# Shield-0_6.net
KiCad netlist of a schematic drawn in EAGLE
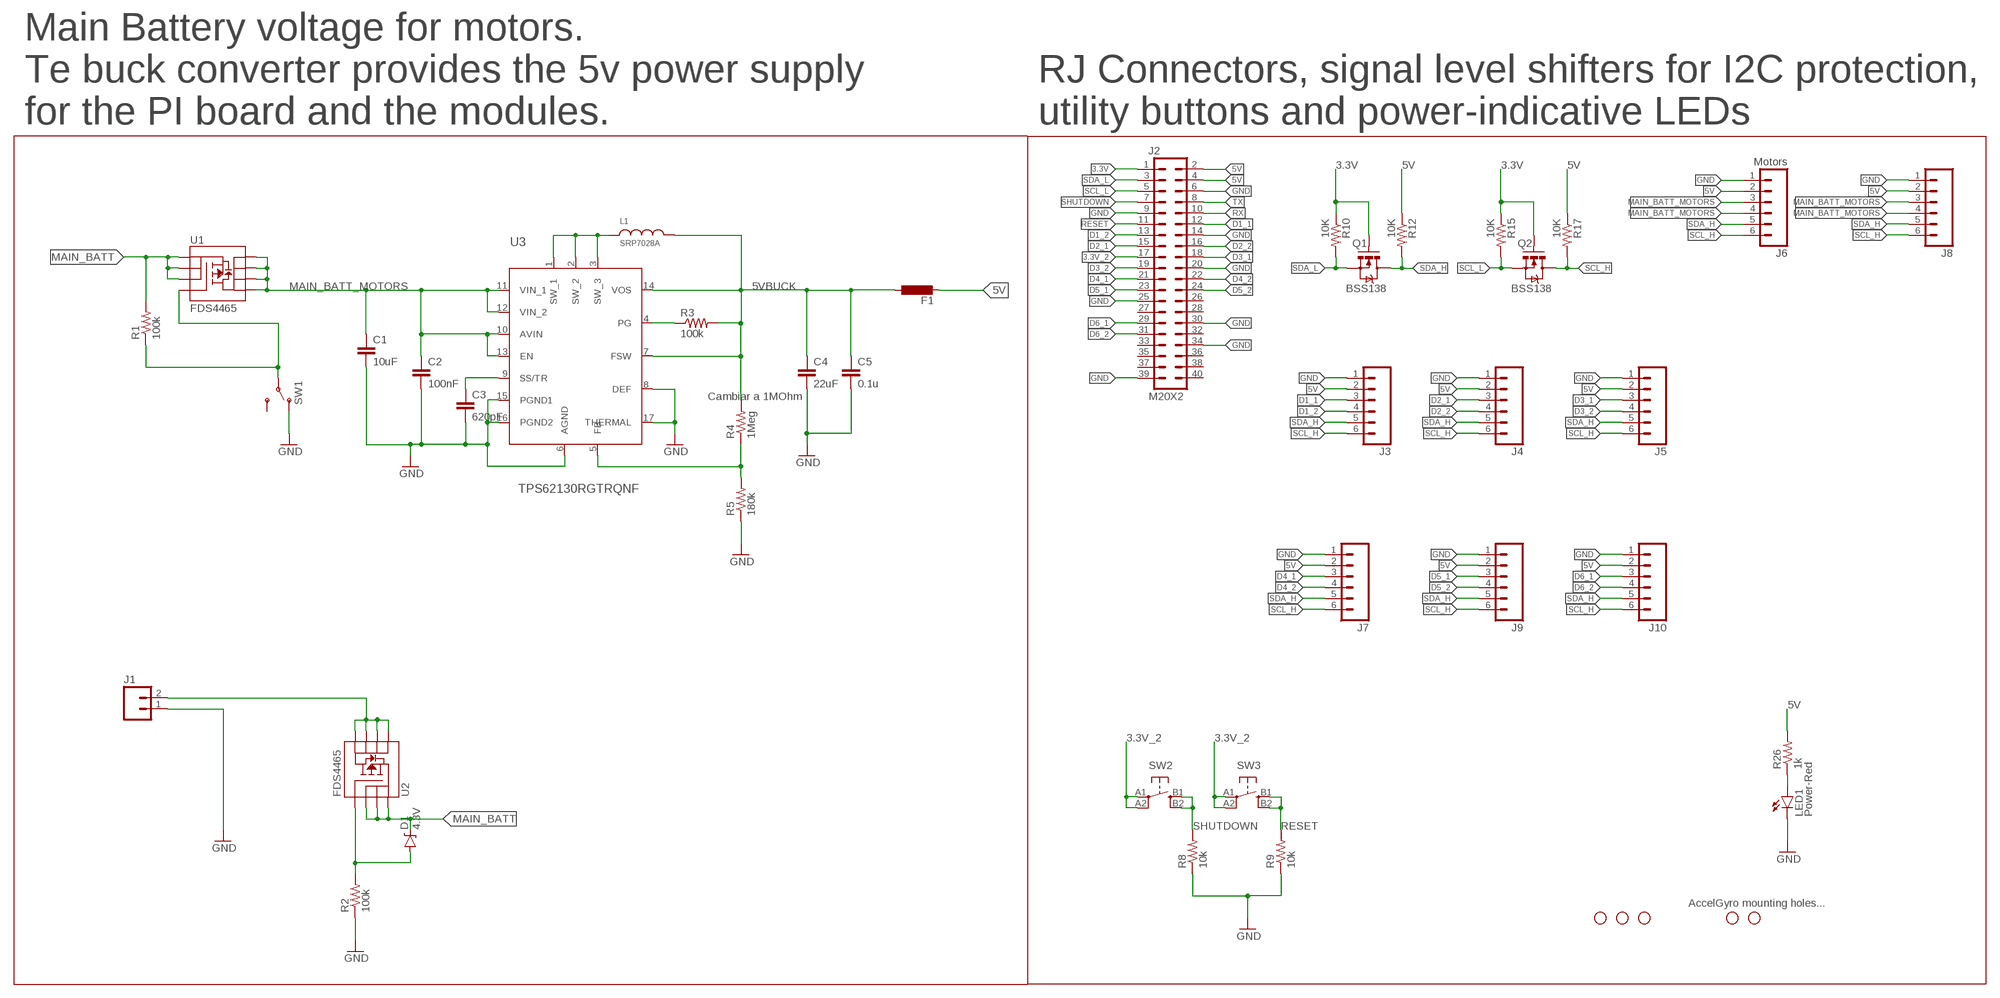
[diagram p0: schematic, sheet 1]

(export (version "E")
  (design (tool "Eeschema 10.0.6"))
  (components
    (comp (ref "C1")
      (value "10uF")
      (footprint "eagle-import:0603-CAP")
      (libsource (lib "eagle-import") (part "CAP0603-CAP"))
    )
    (comp (ref "C2")
      (value "100nF")
      (footprint "eagle-import:0603-CAP")
      (libsource (lib "eagle-import") (part "CAP0603-CAP"))
    )
    (comp (ref "C3")
      (value "620pF")
      (footprint "eagle-import:0603-CAP")
      (libsource (lib "eagle-import") (part "CAP0603-CAP"))
    )
    (comp (ref "C4")
      (value "22uF")
      (footprint "eagle-import:0805")
      (libsource (lib "eagle-import") (part "SparkFun-Passives_CAP0805"))
    )
    (comp (ref "C5")
      (value "0.1u")
      (footprint "eagle-import:0603-CAP")
      (libsource (lib "eagle-import") (part "CAP0603-CAP"))
    )
    (comp (ref "D1")
      (value "4.3V")
      (footprint "eagle-import:SOD-323")
      (libsource (lib "eagle-import") (part "DIODE-ZENER3.3V"))
    )
    (comp (ref "F1")
      (value "L-EUL1812")
      (footprint "eagle-import:L1812")
      (libsource (lib "eagle-import") (part "L-EUL1812"))
    )
    (comp (ref "H1")
      (value "STAND-OFFPLATED")
      (footprint "eagle-import:STAND-OFF-PLATED")
      (libsource (lib "eagle-import") (part "STAND-OFFPLATED"))
    )
    (comp (ref "H2")
      (value "STAND-OFFPLATED")
      (footprint "eagle-import:STAND-OFF-PLATED")
      (libsource (lib "eagle-import") (part "STAND-OFFPLATED"))
    )
    (comp (ref "H3")
      (value "STAND-OFFNORMAL")
      (footprint "eagle-import:STAND-OFF")
      (libsource (lib "eagle-import") (part "STAND-OFFNORMAL"))
    )
    (comp (ref "H4")
      (value "STAND-OFF")
      (footprint "eagle-import:STAND-OFF")
      (libsource (lib "eagle-import") (part "STAND-OFF"))
    )
    (comp (ref "H5")
      (value "STAND-OFF")
      (footprint "eagle-import:STAND-OFF")
      (libsource (lib "eagle-import") (part "STAND-OFF"))
    )
    (comp (ref "J1")
      (value "M02PTH-XH")
      (footprint "eagle-import:JST-2-PTH-XH")
      (libsource (lib "eagle-import") (part "M02PTH-XH"))
    )
    (comp (ref "J2")
      (value "M20X2")
      (footprint "eagle-import:2X20")
      (libsource (lib "eagle-import") (part "M20X2"))
    )
    (comp (ref "J3")
      (value "M06RJ11")
      (footprint "eagle-import:RJ11-6P6C")
      (libsource (lib "eagle-import") (part "M06RJ11"))
    )
    (comp (ref "J4")
      (value "M06RJ11")
      (footprint "eagle-import:RJ11-6P6C")
      (libsource (lib "eagle-import") (part "M06RJ11"))
    )
    (comp (ref "J5")
      (value "M06RJ11")
      (footprint "eagle-import:RJ11-6P6C")
      (libsource (lib "eagle-import") (part "M06RJ11"))
    )
    (comp (ref "J6")
      (value "Motors")
      (footprint "eagle-import:RJ11-6P6C")
      (libsource (lib "eagle-import") (part "M06RJ11"))
    )
    (comp (ref "J7")
      (value "M06RJ11")
      (footprint "eagle-import:RJ11-6P6C")
      (libsource (lib "eagle-import") (part "M06RJ11"))
    )
    (comp (ref "J8")
      (value "M06RJ11")
      (footprint "eagle-import:RJ11-6P6C")
      (libsource (lib "eagle-import") (part "M06RJ11"))
    )
    (comp (ref "J9")
      (value "M06RJ11-SMD")
      (footprint "eagle-import:RJ11-6P6C-SMD")
      (libsource (lib "eagle-import") (part "M06RJ11-SMD"))
    )
    (comp (ref "J10")
      (value "M06RJ11-SMD")
      (footprint "eagle-import:RJ11-6P6C-SMD")
      (libsource (lib "eagle-import") (part "M06RJ11-SMD"))
    )
    (comp (ref "L1")
      (value "SRP7028A")
      (footprint "eagle-import:SRP7028A")
      (libsource (lib "eagle-import") (part "SRP7028A"))
    )
    (comp (ref "LED1")
      (value "Power-Red")
      (footprint "eagle-import:LED-0603")
      (libsource (lib "eagle-import") (part "LED0603"))
    )
    (comp (ref "Q1")
      (value "BSS138")
      (footprint "eagle-import:SOT23-3")
      (libsource (lib "eagle-import") (part "MOSFET-NCHANNELSMD"))
    )
    (comp (ref "Q2")
      (value "BSS138")
      (footprint "eagle-import:SOT23-3")
      (libsource (lib "eagle-import") (part "MOSFET-NCHANNELSMD"))
    )
    (comp (ref "R1")
      (value "100k")
      (footprint "eagle-import:0603-RES")
      (libsource (lib "eagle-import") (part "RESISTOR0603-RES"))
    )
    (comp (ref "R2")
      (value "100k")
      (footprint "eagle-import:0603-RES")
      (libsource (lib "eagle-import") (part "RESISTOR0603-RES"))
    )
    (comp (ref "R3")
      (value "100k")
      (footprint "eagle-import:0603-RES")
      (libsource (lib "eagle-import") (part "RESISTOR0603-RES"))
    )
    (comp (ref "R4")
      (value "1Meg")
      (footprint "eagle-import:0603-RES")
      (libsource (lib "eagle-import") (part "RESISTOR0603-RES"))
    )
    (comp (ref "R5")
      (value "180k")
      (footprint "eagle-import:0603-RES")
      (libsource (lib "eagle-import") (part "RESISTOR0603-RES"))
    )
    (comp (ref "R8")
      (value "10k")
      (footprint "eagle-import:0603-RES")
      (libsource (lib "eagle-import") (part "RESISTOR0603-RES"))
    )
    (comp (ref "R9")
      (value "10k")
      (footprint "eagle-import:0603-RES")
      (libsource (lib "eagle-import") (part "RESISTOR0603-RES"))
    )
    (comp (ref "R10")
      (value "10K")
      (footprint "eagle-import:0603-RES")
      (libsource (lib "eagle-import") (part "RESISTOR0603-RES"))
    )
    (comp (ref "R12")
      (value "10K")
      (footprint "eagle-import:0603-RES")
      (libsource (lib "eagle-import") (part "RESISTOR0603-RES"))
    )
    (comp (ref "R15")
      (value "10K")
      (footprint "eagle-import:0603-RES")
      (libsource (lib "eagle-import") (part "RESISTOR0603-RES"))
    )
    (comp (ref "R17")
      (value "10K")
      (footprint "eagle-import:0603-RES")
      (libsource (lib "eagle-import") (part "RESISTOR0603-RES"))
    )
    (comp (ref "R26")
      (value "1k")
      (footprint "eagle-import:0603-RES")
      (libsource (lib "eagle-import") (part "RESISTOR0603-RES"))
    )
    (comp (ref "SW1")
      (value "SWITCH-SPDT-SPDT-TH")
      (footprint "eagle-import:SW-SPDT-TH")
      (libsource (lib "eagle-import") (part "SWITCH-SPDT-SPDT-TH"))
    )
    (comp (ref "SW2")
      (value "SWITCH_SPST_4_PINTALL")
      (footprint "eagle-import:TACTILE_SWITCH_TALL")
      (libsource (lib "eagle-import") (part "SWITCH_SPST_4_PINTALL"))
    )
    (comp (ref "SW3")
      (value "SWITCH_SPST_4_PINTALL")
      (footprint "eagle-import:TACTILE_SWITCH_TALL")
      (libsource (lib "eagle-import") (part "SWITCH_SPST_4_PINTALL"))
    )
    (comp (ref "U1")
      (value "FDS4465")
      (footprint "eagle-import:SO08")
      (libsource (lib "eagle-import") (part "MOSFET-PCHANNEL-SOIC8SOIC8"))
    )
    (comp (ref "U2")
      (value "FDS4465")
      (footprint "eagle-import:SO08")
      (libsource (lib "eagle-import") (part "MOSFET-PCHANNEL-SOIC8SOIC8"))
    )
    (comp (ref "U3")
      (value "TPS62130RGTRQNF")
      (footprint "eagle-import:QFN-N16")
      (libsource (lib "eagle-import") (part "TPS62130RGTRQNF"))
    )
  )
  (nets
    (net (code "1") (name "/5VBUCK") (class "Default")
      (node (ref "C4") (pin "1") (pinfunction "1_1") (pintype "passive"))
      (node (ref "C5") (pin "1") (pinfunction "1_1") (pintype "passive"))
      (node (ref "F1") (pin "1") (pinfunction "1_1") (pintype "passive"))
      (node (ref "L1") (pin "P$2") (pinfunction "2_P$2") (pintype "bidirectional"))
      (node (ref "R3") (pin "2") (pinfunction "2_2") (pintype "passive"))
      (node (ref "R4") (pin "2") (pinfunction "2_2") (pintype "passive"))
      (node (ref "U3") (pin "14") (pinfunction "VOS_14") (pintype "passive"))
      (node (ref "U3") (pin "7") (pinfunction "FSW_7") (pintype "passive"))
    )
    (net (code "2") (name "3.3V") (class "Default")
      (node (ref "J2") (pin "1") (pinfunction "1_1") (pintype "passive"))
      (node (ref "Q1") (pin "1") (pinfunction "G_1") (pintype "passive"))
      (node (ref "Q2") (pin "1") (pinfunction "G_1") (pintype "passive"))
      (node (ref "R10") (pin "1") (pinfunction "1_1") (pintype "passive"))
      (node (ref "R15") (pin "1") (pinfunction "1_1") (pintype "passive"))
    )
    (net (code "3") (name "3.3V_2") (class "Default")
      (node (ref "J2") (pin "17") (pinfunction "17_17") (pintype "passive"))
      (node (ref "SW2") (pin "A1") (pinfunction "1_A1") (pintype "passive"))
      (node (ref "SW2") (pin "A2") (pinfunction "2_A2") (pintype "passive"))
      (node (ref "SW3") (pin "A1") (pinfunction "1_A1") (pintype "passive"))
      (node (ref "SW3") (pin "A2") (pinfunction "2_A2") (pintype "passive"))
    )
    (net (code "4") (name "5V") (class "Default")
      (node (ref "F1") (pin "2") (pinfunction "2_2") (pintype "passive"))
      (node (ref "J10") (pin "2") (pinfunction "2_2") (pintype "passive"))
      (node (ref "J2") (pin "2") (pinfunction "2_2") (pintype "passive"))
      (node (ref "J2") (pin "4") (pinfunction "4_4") (pintype "passive"))
      (node (ref "J3") (pin "2") (pinfunction "2_2") (pintype "passive"))
      (node (ref "J4") (pin "2") (pinfunction "2_2") (pintype "passive"))
      (node (ref "J5") (pin "2") (pinfunction "2_2") (pintype "passive"))
      (node (ref "J6") (pin "2") (pinfunction "2_2") (pintype "passive"))
      (node (ref "J7") (pin "2") (pinfunction "2_2") (pintype "passive"))
      (node (ref "J8") (pin "2") (pinfunction "2_2") (pintype "passive"))
      (node (ref "J9") (pin "2") (pinfunction "2_2") (pintype "passive"))
      (node (ref "R12") (pin "1") (pinfunction "1_1") (pintype "passive"))
      (node (ref "R17") (pin "1") (pinfunction "1_1") (pintype "passive"))
      (node (ref "R26") (pin "2") (pinfunction "2_2") (pintype "passive"))
    )
    (net (code "5") (name "D1_1") (class "Default")
      (node (ref "J2") (pin "12") (pinfunction "12_12") (pintype "passive"))
      (node (ref "J3") (pin "3") (pinfunction "3_3") (pintype "passive"))
    )
    (net (code "6") (name "D1_2") (class "Default")
      (node (ref "J2") (pin "13") (pinfunction "13_13") (pintype "passive"))
      (node (ref "J3") (pin "4") (pinfunction "4_4") (pintype "passive"))
    )
    (net (code "7") (name "D2_1") (class "Default")
      (node (ref "J2") (pin "15") (pinfunction "15_15") (pintype "passive"))
      (node (ref "J4") (pin "3") (pinfunction "3_3") (pintype "passive"))
    )
    (net (code "8") (name "D2_2") (class "Default")
      (node (ref "J2") (pin "16") (pinfunction "16_16") (pintype "passive"))
      (node (ref "J4") (pin "4") (pinfunction "4_4") (pintype "passive"))
    )
    (net (code "9") (name "D3_1") (class "Default")
      (node (ref "J2") (pin "18") (pinfunction "18_18") (pintype "passive"))
      (node (ref "J5") (pin "3") (pinfunction "3_3") (pintype "passive"))
    )
    (net (code "10") (name "D3_2") (class "Default")
      (node (ref "J2") (pin "19") (pinfunction "19_19") (pintype "passive"))
      (node (ref "J5") (pin "4") (pinfunction "4_4") (pintype "passive"))
    )
    (net (code "11") (name "D4_1") (class "Default")
      (node (ref "J2") (pin "21") (pinfunction "21_21") (pintype "passive"))
      (node (ref "J7") (pin "3") (pinfunction "3_3") (pintype "passive"))
    )
    (net (code "12") (name "D4_2") (class "Default")
      (node (ref "J2") (pin "22") (pinfunction "22_22") (pintype "passive"))
      (node (ref "J7") (pin "4") (pinfunction "4_4") (pintype "passive"))
    )
    (net (code "13") (name "D5_1") (class "Default")
      (node (ref "J2") (pin "23") (pinfunction "23_23") (pintype "passive"))
      (node (ref "J9") (pin "3") (pinfunction "3_3") (pintype "passive"))
    )
    (net (code "14") (name "D5_2") (class "Default")
      (node (ref "J2") (pin "24") (pinfunction "24_24") (pintype "passive"))
      (node (ref "J9") (pin "4") (pinfunction "4_4") (pintype "passive"))
    )
    (net (code "15") (name "D6_1") (class "Default")
      (node (ref "J10") (pin "3") (pinfunction "3_3") (pintype "passive"))
      (node (ref "J2") (pin "29") (pinfunction "29_29") (pintype "passive"))
    )
    (net (code "16") (name "D6_2") (class "Default")
      (node (ref "J10") (pin "4") (pinfunction "4_4") (pintype "passive"))
      (node (ref "J2") (pin "31") (pinfunction "31_31") (pintype "passive"))
    )
    (net (code "17") (name "GND") (class "Default")
      (node (ref "C1") (pin "2") (pinfunction "2_2") (pintype "passive"))
      (node (ref "C2") (pin "2") (pinfunction "2_2") (pintype "passive"))
      (node (ref "C3") (pin "2") (pinfunction "2_2") (pintype "passive"))
      (node (ref "C4") (pin "2") (pinfunction "2_2") (pintype "passive"))
      (node (ref "C5") (pin "2") (pinfunction "2_2") (pintype "passive"))
      (node (ref "J1") (pin "1") (pinfunction "1_1") (pintype "passive"))
      (node (ref "J10") (pin "1") (pinfunction "1_1") (pintype "passive"))
      (node (ref "J2") (pin "14") (pinfunction "14_14") (pintype "passive"))
      (node (ref "J2") (pin "20") (pinfunction "20_20") (pintype "passive"))
      (node (ref "J2") (pin "25") (pinfunction "25_25") (pintype "passive"))
      (node (ref "J2") (pin "30") (pinfunction "30_30") (pintype "passive"))
      (node (ref "J2") (pin "34") (pinfunction "34_34") (pintype "passive"))
      (node (ref "J2") (pin "39") (pinfunction "39_39") (pintype "passive"))
      (node (ref "J2") (pin "6") (pinfunction "6_6") (pintype "passive"))
      (node (ref "J2") (pin "9") (pinfunction "9_9") (pintype "passive"))
      (node (ref "J3") (pin "1") (pinfunction "1_1") (pintype "passive"))
      (node (ref "J4") (pin "1") (pinfunction "1_1") (pintype "passive"))
      (node (ref "J5") (pin "1") (pinfunction "1_1") (pintype "passive"))
      (node (ref "J6") (pin "1") (pinfunction "1_1") (pintype "passive"))
      (node (ref "J7") (pin "1") (pinfunction "1_1") (pintype "passive"))
      (node (ref "J8") (pin "1") (pinfunction "1_1") (pintype "passive"))
      (node (ref "J9") (pin "1") (pinfunction "1_1") (pintype "passive"))
      (node (ref "LED1") (pin "C") (pinfunction "C_C") (pintype "passive"))
      (node (ref "R2") (pin "1") (pinfunction "1_1") (pintype "passive"))
      (node (ref "R5") (pin "1") (pinfunction "1_1") (pintype "passive"))
      (node (ref "R8") (pin "1") (pinfunction "1_1") (pintype "passive"))
      (node (ref "R9") (pin "1") (pinfunction "1_1") (pintype "passive"))
      (node (ref "SW1") (pin "P$3") (pinfunction "O_P$3") (pintype "passive"))
      (node (ref "U3") (pin "15") (pinfunction "PGND1_15") (pintype "passive"))
      (node (ref "U3") (pin "16") (pinfunction "PGND2_16") (pintype "bidirectional"))
      (node (ref "U3") (pin "17") (pinfunction "THERMAL_17") (pintype "bidirectional"))
      (node (ref "U3") (pin "6") (pinfunction "AGND_6") (pintype "passive"))
      (node (ref "U3") (pin "8") (pinfunction "DEF_8") (pintype "passive"))
    )
    (net (code "18") (name "MAIN_BATT") (class "Default")
      (node (ref "D1") (pin "C") (pinfunction "C_C") (pintype "passive"))
      (node (ref "R1") (pin "2") (pinfunction "2_2") (pintype "passive"))
      (node (ref "U1") (pin "1") (pinfunction "S_1") (pintype "bidirectional"))
      (node (ref "U1") (pin "2") (pinfunction "S_2") (pintype "bidirectional"))
      (node (ref "U1") (pin "3") (pinfunction "S_3") (pintype "bidirectional"))
      (node (ref "U2") (pin "1") (pinfunction "S_1") (pintype "bidirectional"))
      (node (ref "U2") (pin "2") (pinfunction "S_2") (pintype "bidirectional"))
      (node (ref "U2") (pin "3") (pinfunction "S_3") (pintype "bidirectional"))
    )
    (net (code "19") (name "MAIN_BATT_MOTORS") (class "Default")
      (node (ref "C1") (pin "1") (pinfunction "1_1") (pintype "passive"))
      (node (ref "C2") (pin "1") (pinfunction "1_1") (pintype "passive"))
      (node (ref "J6") (pin "3") (pinfunction "3_3") (pintype "passive"))
      (node (ref "J6") (pin "4") (pinfunction "4_4") (pintype "passive"))
      (node (ref "J8") (pin "3") (pinfunction "3_3") (pintype "passive"))
      (node (ref "J8") (pin "4") (pinfunction "4_4") (pintype "passive"))
      (node (ref "U1") (pin "5") (pinfunction "D_5") (pintype "bidirectional"))
      (node (ref "U1") (pin "6") (pinfunction "D_6") (pintype "bidirectional"))
      (node (ref "U1") (pin "7") (pinfunction "D_7") (pintype "bidirectional"))
      (node (ref "U1") (pin "8") (pinfunction "D_8") (pintype "bidirectional"))
      (node (ref "U3") (pin "10") (pinfunction "AVIN_10") (pintype "passive"))
      (node (ref "U3") (pin "11") (pinfunction "VIN_1_11") (pintype "passive"))
      (node (ref "U3") (pin "12") (pinfunction "VIN_2_12") (pintype "passive"))
      (node (ref "U3") (pin "13") (pinfunction "EN_13") (pintype "passive"))
    )
    (net (code "20") (name "Net-(J1-Pad2)") (class "Default")
      (node (ref "J1") (pin "2") (pinfunction "2_2") (pintype "passive"))
      (node (ref "U2") (pin "5") (pinfunction "D_5") (pintype "bidirectional"))
      (node (ref "U2") (pin "6") (pinfunction "D_6") (pintype "bidirectional"))
      (node (ref "U2") (pin "7") (pinfunction "D_7") (pintype "bidirectional"))
      (node (ref "U2") (pin "8") (pinfunction "D_8") (pintype "bidirectional"))
    )
    (net (code "21") (name "Net-(L1-1)") (class "Default")
      (node (ref "L1") (pin "P$1") (pinfunction "1_P$1") (pintype "bidirectional"))
      (node (ref "U3") (pin "1") (pinfunction "SW_1_1") (pintype "passive"))
      (node (ref "U3") (pin "2") (pinfunction "SW_2_2") (pintype "passive"))
      (node (ref "U3") (pin "3") (pinfunction "SW_3_3") (pintype "passive"))
    )
    (net (code "22") (name "Net-(LED1-PadA)") (class "Default")
      (node (ref "LED1") (pin "A") (pinfunction "A_A") (pintype "passive"))
      (node (ref "R26") (pin "1") (pinfunction "1_1") (pintype "passive"))
    )
    (net (code "23") (name "Net-(SW1-P)") (class "Default")
      (node (ref "R1") (pin "1") (pinfunction "1_1") (pintype "passive"))
      (node (ref "SW1") (pin "P$2") (pinfunction "P_P$2") (pintype "passive"))
      (node (ref "U1") (pin "4") (pinfunction "G_4") (pintype "bidirectional"))
    )
    (net (code "24") (name "Net-(U2-G)") (class "Default")
      (node (ref "D1") (pin "A") (pinfunction "A_A") (pintype "passive"))
      (node (ref "R2") (pin "2") (pinfunction "2_2") (pintype "passive"))
      (node (ref "U2") (pin "4") (pinfunction "G_4") (pintype "bidirectional"))
    )
    (net (code "25") (name "Net-(U3-FB)") (class "Default")
      (node (ref "R4") (pin "1") (pinfunction "1_1") (pintype "passive"))
      (node (ref "R5") (pin "2") (pinfunction "2_2") (pintype "passive"))
      (node (ref "U3") (pin "5") (pinfunction "FB_5") (pintype "passive"))
    )
    (net (code "26") (name "Net-(U3-PG)") (class "Default")
      (node (ref "R3") (pin "1") (pinfunction "1_1") (pintype "passive"))
      (node (ref "U3") (pin "4") (pinfunction "PG_4") (pintype "passive"))
    )
    (net (code "27") (name "Net-(U3-SS{slash}TR)") (class "Default")
      (node (ref "C3") (pin "1") (pinfunction "1_1") (pintype "passive"))
      (node (ref "U3") (pin "9") (pinfunction "SS/TR_9") (pintype "passive"))
    )
    (net (code "28") (name "RESET") (class "Default")
      (node (ref "J2") (pin "11") (pinfunction "11_11") (pintype "passive"))
      (node (ref "R9") (pin "2") (pinfunction "2_2") (pintype "passive"))
      (node (ref "SW3") (pin "B1") (pinfunction "3_B1") (pintype "passive"))
      (node (ref "SW3") (pin "B2") (pinfunction "4_B2") (pintype "passive"))
    )
    (net (code "29") (name "RX") (class "Default")
      (node (ref "J2") (pin "10") (pinfunction "10_10") (pintype "passive"))
    )
    (net (code "30") (name "SCL_H") (class "Default")
      (node (ref "J10") (pin "6") (pinfunction "6_6") (pintype "passive"))
      (node (ref "J3") (pin "6") (pinfunction "6_6") (pintype "passive"))
      (node (ref "J4") (pin "6") (pinfunction "6_6") (pintype "passive"))
      (node (ref "J5") (pin "6") (pinfunction "6_6") (pintype "passive"))
      (node (ref "J6") (pin "6") (pinfunction "6_6") (pintype "passive"))
      (node (ref "J7") (pin "6") (pinfunction "6_6") (pintype "passive"))
      (node (ref "J8") (pin "6") (pinfunction "6_6") (pintype "passive"))
      (node (ref "J9") (pin "6") (pinfunction "6_6") (pintype "passive"))
      (node (ref "Q2") (pin "3") (pinfunction "D_3") (pintype "passive"))
      (node (ref "R17") (pin "2") (pinfunction "2_2") (pintype "passive"))
    )
    (net (code "31") (name "SCL_L") (class "Default")
      (node (ref "J2") (pin "5") (pinfunction "5_5") (pintype "passive"))
      (node (ref "Q2") (pin "2") (pinfunction "S_2") (pintype "passive"))
      (node (ref "R15") (pin "2") (pinfunction "2_2") (pintype "passive"))
    )
    (net (code "32") (name "SDA_H") (class "Default")
      (node (ref "J10") (pin "5") (pinfunction "5_5") (pintype "passive"))
      (node (ref "J3") (pin "5") (pinfunction "5_5") (pintype "passive"))
      (node (ref "J4") (pin "5") (pinfunction "5_5") (pintype "passive"))
      (node (ref "J5") (pin "5") (pinfunction "5_5") (pintype "passive"))
      (node (ref "J6") (pin "5") (pinfunction "5_5") (pintype "passive"))
      (node (ref "J7") (pin "5") (pinfunction "5_5") (pintype "passive"))
      (node (ref "J8") (pin "5") (pinfunction "5_5") (pintype "passive"))
      (node (ref "J9") (pin "5") (pinfunction "5_5") (pintype "passive"))
      (node (ref "Q1") (pin "3") (pinfunction "D_3") (pintype "passive"))
      (node (ref "R12") (pin "2") (pinfunction "2_2") (pintype "passive"))
    )
    (net (code "33") (name "SDA_L") (class "Default")
      (node (ref "J2") (pin "3") (pinfunction "3_3") (pintype "passive"))
      (node (ref "Q1") (pin "2") (pinfunction "S_2") (pintype "passive"))
      (node (ref "R10") (pin "2") (pinfunction "2_2") (pintype "passive"))
    )
    (net (code "34") (name "SHUTDOWN") (class "Default")
      (node (ref "J2") (pin "7") (pinfunction "7_7") (pintype "passive"))
      (node (ref "R8") (pin "2") (pinfunction "2_2") (pintype "passive"))
      (node (ref "SW2") (pin "B1") (pinfunction "3_B1") (pintype "passive"))
      (node (ref "SW2") (pin "B2") (pinfunction "4_B2") (pintype "passive"))
    )
    (net (code "35") (name "TX") (class "Default")
      (node (ref "J2") (pin "8") (pinfunction "8_8") (pintype "passive"))
    )
    (net (code "36") (name "unconnected-(J2-Pad26)") (class "Default")
      (node (ref "J2") (pin "26") (pinfunction "26_26") (pintype "passive"))
    )
    (net (code "37") (name "unconnected-(J2-Pad27)") (class "Default")
      (node (ref "J2") (pin "27") (pinfunction "27_27") (pintype "passive"))
    )
    (net (code "38") (name "unconnected-(J2-Pad28)") (class "Default")
      (node (ref "J2") (pin "28") (pinfunction "28_28") (pintype "passive"))
    )
    (net (code "39") (name "unconnected-(J2-Pad32)") (class "Default")
      (node (ref "J2") (pin "32") (pinfunction "32_32") (pintype "passive"))
    )
    (net (code "40") (name "unconnected-(J2-Pad33)") (class "Default")
      (node (ref "J2") (pin "33") (pinfunction "33_33") (pintype "passive"))
    )
    (net (code "41") (name "unconnected-(J2-Pad35)") (class "Default")
      (node (ref "J2") (pin "35") (pinfunction "35_35") (pintype "passive"))
    )
    (net (code "42") (name "unconnected-(J2-Pad36)") (class "Default")
      (node (ref "J2") (pin "36") (pinfunction "36_36") (pintype "passive"))
    )
    (net (code "43") (name "unconnected-(J2-Pad37)") (class "Default")
      (node (ref "J2") (pin "37") (pinfunction "37_37") (pintype "passive"))
    )
    (net (code "44") (name "unconnected-(J2-Pad38)") (class "Default")
      (node (ref "J2") (pin "38") (pinfunction "38_38") (pintype "passive"))
    )
    (net (code "45") (name "unconnected-(J2-Pad40)") (class "Default")
      (node (ref "J2") (pin "40") (pinfunction "40_40") (pintype "passive"))
    )
    (net (code "46") (name "unconnected-(SW1-S-PadP$1)") (class "Default")
      (node (ref "SW1") (pin "P$1") (pinfunction "S_P$1") (pintype "passive"))
    )
  )
)
